# driverV3.net
KiCad netlist of a schematic drawn in EAGLE
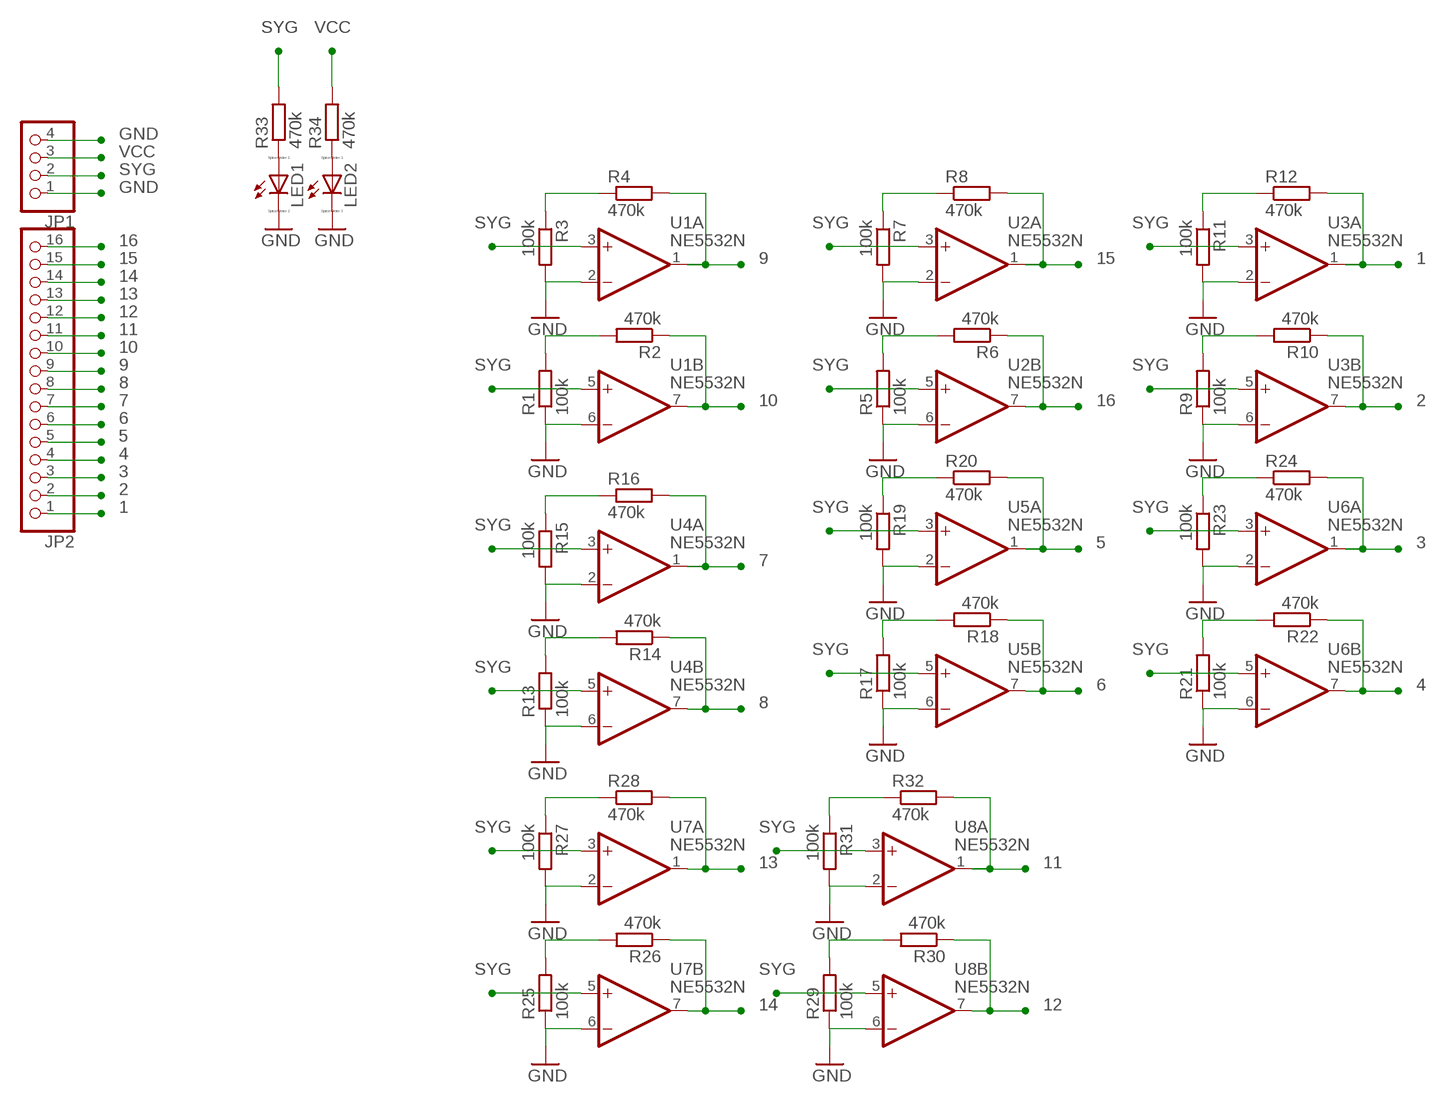
[diagram p0: schematic, sheet 1]

(export (version "E")
  (design (tool "Eeschema 10.0.6"))
  (components
    (comp (ref "JP1")
      (value "PINHD-1X4")
      (footprint "eagle-import:1X04")
      (libsource (lib "eagle-import") (part "PINHD-1X4"))
    )
    (comp (ref "JP2")
      (value "PINHD-1X16")
      (footprint "eagle-import:1X16")
      (libsource (lib "eagle-import") (part "PINHD-1X16"))
    )
    (comp (ref "LED1")
      (value "LED_ELD260")
      (footprint "eagle-import:LED_LD260")
      (libsource (lib "eagle-import") (part "LED_ELD260"))
    )
    (comp (ref "LED2")
      (value "LED_ELD260")
      (footprint "eagle-import:LED_LD260")
      (libsource (lib "eagle-import") (part "LED_ELD260"))
    )
    (comp (ref "R1")
      (value "100k")
      (footprint "eagle-import:0204_7")
      (libsource (lib "eagle-import") (part "R-EU_0204/7"))
    )
    (comp (ref "R2")
      (value "470k")
      (footprint "eagle-import:0204_7")
      (libsource (lib "eagle-import") (part "R-EU_0204/7"))
    )
    (comp (ref "R3")
      (value "100k")
      (footprint "eagle-import:0204_7")
      (libsource (lib "eagle-import") (part "R-EU_0204/7"))
    )
    (comp (ref "R4")
      (value "470k")
      (footprint "eagle-import:0204_7")
      (libsource (lib "eagle-import") (part "R-EU_0204/7"))
    )
    (comp (ref "R5")
      (value "100k")
      (footprint "eagle-import:0204_7")
      (libsource (lib "eagle-import") (part "R-EU_0204/7"))
    )
    (comp (ref "R6")
      (value "470k")
      (footprint "eagle-import:0204_7")
      (libsource (lib "eagle-import") (part "R-EU_0204/7"))
    )
    (comp (ref "R7")
      (value "100k")
      (footprint "eagle-import:0204_7")
      (libsource (lib "eagle-import") (part "R-EU_0204/7"))
    )
    (comp (ref "R8")
      (value "470k")
      (footprint "eagle-import:0204_7")
      (libsource (lib "eagle-import") (part "R-EU_0204/7"))
    )
    (comp (ref "R9")
      (value "100k")
      (footprint "eagle-import:0204_7")
      (libsource (lib "eagle-import") (part "R-EU_0204/7"))
    )
    (comp (ref "R10")
      (value "470k")
      (footprint "eagle-import:0204_7")
      (libsource (lib "eagle-import") (part "R-EU_0204/7"))
    )
    (comp (ref "R11")
      (value "100k")
      (footprint "eagle-import:0204_7")
      (libsource (lib "eagle-import") (part "R-EU_0204/7"))
    )
    (comp (ref "R12")
      (value "470k")
      (footprint "eagle-import:0204_7")
      (libsource (lib "eagle-import") (part "R-EU_0204/7"))
    )
    (comp (ref "R13")
      (value "100k")
      (footprint "eagle-import:0204_7")
      (libsource (lib "eagle-import") (part "R-EU_0204/7"))
    )
    (comp (ref "R14")
      (value "470k")
      (footprint "eagle-import:0204_7")
      (libsource (lib "eagle-import") (part "R-EU_0204/7"))
    )
    (comp (ref "R15")
      (value "100k")
      (footprint "eagle-import:0204_7")
      (libsource (lib "eagle-import") (part "R-EU_0204/7"))
    )
    (comp (ref "R16")
      (value "470k")
      (footprint "eagle-import:0204_7")
      (libsource (lib "eagle-import") (part "R-EU_0204/7"))
    )
    (comp (ref "R17")
      (value "100k")
      (footprint "eagle-import:0204_7")
      (libsource (lib "eagle-import") (part "R-EU_0204/7"))
    )
    (comp (ref "R18")
      (value "470k")
      (footprint "eagle-import:0204_7")
      (libsource (lib "eagle-import") (part "R-EU_0204/7"))
    )
    (comp (ref "R19")
      (value "100k")
      (footprint "eagle-import:0204_7")
      (libsource (lib "eagle-import") (part "R-EU_0204/7"))
    )
    (comp (ref "R20")
      (value "470k")
      (footprint "eagle-import:0204_7")
      (libsource (lib "eagle-import") (part "R-EU_0204/7"))
    )
    (comp (ref "R21")
      (value "100k")
      (footprint "eagle-import:0204_7")
      (libsource (lib "eagle-import") (part "R-EU_0204/7"))
    )
    (comp (ref "R22")
      (value "470k")
      (footprint "eagle-import:0204_7")
      (libsource (lib "eagle-import") (part "R-EU_0204/7"))
    )
    (comp (ref "R23")
      (value "100k")
      (footprint "eagle-import:0204_7")
      (libsource (lib "eagle-import") (part "R-EU_0204/7"))
    )
    (comp (ref "R24")
      (value "470k")
      (footprint "eagle-import:0204_7")
      (libsource (lib "eagle-import") (part "R-EU_0204/7"))
    )
    (comp (ref "R25")
      (value "100k")
      (footprint "eagle-import:0204_7")
      (libsource (lib "eagle-import") (part "R-EU_0204/7"))
    )
    (comp (ref "R26")
      (value "470k")
      (footprint "eagle-import:0204_7")
      (libsource (lib "eagle-import") (part "R-EU_0204/7"))
    )
    (comp (ref "R27")
      (value "100k")
      (footprint "eagle-import:0204_7")
      (libsource (lib "eagle-import") (part "R-EU_0204/7"))
    )
    (comp (ref "R28")
      (value "470k")
      (footprint "eagle-import:0204_7")
      (libsource (lib "eagle-import") (part "R-EU_0204/7"))
    )
    (comp (ref "R29")
      (value "100k")
      (footprint "eagle-import:0204_7")
      (libsource (lib "eagle-import") (part "R-EU_0204/7"))
    )
    (comp (ref "R30")
      (value "470k")
      (footprint "eagle-import:0204_7")
      (libsource (lib "eagle-import") (part "R-EU_0204/7"))
    )
    (comp (ref "R31")
      (value "100k")
      (footprint "eagle-import:0204_7")
      (libsource (lib "eagle-import") (part "R-EU_0204/7"))
    )
    (comp (ref "R32")
      (value "470k")
      (footprint "eagle-import:0204_7")
      (libsource (lib "eagle-import") (part "R-EU_0204/7"))
    )
    (comp (ref "R33")
      (value "470k")
      (footprint "eagle-import:0204_7")
      (libsource (lib "eagle-import") (part "R-EU_0204/7"))
    )
    (comp (ref "R34")
      (value "470k")
      (footprint "eagle-import:0204_7")
      (libsource (lib "eagle-import") (part "R-EU_0204/7"))
    )
    (comp (ref "U1")
      (value "NE5532N")
      (footprint "eagle-import:DIL08")
      (libsource (lib "eagle-import") (part "NE5532N"))
    )
    (comp (ref "U2")
      (value "NE5532N")
      (footprint "eagle-import:DIL08")
      (libsource (lib "eagle-import") (part "NE5532N"))
    )
    (comp (ref "U3")
      (value "NE5532N")
      (footprint "eagle-import:DIL08")
      (libsource (lib "eagle-import") (part "NE5532N"))
    )
    (comp (ref "U4")
      (value "NE5532N")
      (footprint "eagle-import:DIL08")
      (libsource (lib "eagle-import") (part "NE5532N"))
    )
    (comp (ref "U5")
      (value "NE5532N")
      (footprint "eagle-import:DIL08")
      (libsource (lib "eagle-import") (part "NE5532N"))
    )
    (comp (ref "U6")
      (value "NE5532N")
      (footprint "eagle-import:DIL08")
      (libsource (lib "eagle-import") (part "NE5532N"))
    )
    (comp (ref "U7")
      (value "NE5532N")
      (footprint "eagle-import:DIL08")
      (libsource (lib "eagle-import") (part "NE5532N"))
    )
    (comp (ref "U8")
      (value "NE5532N")
      (footprint "eagle-import:DIL08")
      (libsource (lib "eagle-import") (part "NE5532N"))
    )
  )
  (nets
    (net (code "1") (name "/1") (class "Default")
      (node (ref "JP2") (pin "1") (pinfunction "1_1") (pintype "passive"))
      (node (ref "R12") (pin "2") (pinfunction "2_2") (pintype "passive"))
      (node (ref "U3") (pin "1") (pinfunction "OUT_1") (pintype "output"))
    )
    (net (code "2") (name "/2") (class "Default")
      (node (ref "JP2") (pin "2") (pinfunction "2_2") (pintype "passive"))
      (node (ref "R10") (pin "1") (pinfunction "1_1") (pintype "passive"))
      (node (ref "U3") (pin "7") (pinfunction "OUT_7") (pintype "output"))
    )
    (net (code "3") (name "/3") (class "Default")
      (node (ref "JP2") (pin "3") (pinfunction "3_3") (pintype "passive"))
      (node (ref "R24") (pin "2") (pinfunction "2_2") (pintype "passive"))
      (node (ref "U6") (pin "1") (pinfunction "OUT_1") (pintype "output"))
    )
    (net (code "4") (name "/4") (class "Default")
      (node (ref "JP2") (pin "4") (pinfunction "4_4") (pintype "passive"))
      (node (ref "R22") (pin "1") (pinfunction "1_1") (pintype "passive"))
      (node (ref "U6") (pin "7") (pinfunction "OUT_7") (pintype "output"))
    )
    (net (code "5") (name "/5") (class "Default")
      (node (ref "JP2") (pin "5") (pinfunction "5_5") (pintype "passive"))
      (node (ref "R20") (pin "2") (pinfunction "2_2") (pintype "passive"))
      (node (ref "U5") (pin "1") (pinfunction "OUT_1") (pintype "output"))
    )
    (net (code "6") (name "/6") (class "Default")
      (node (ref "JP2") (pin "6") (pinfunction "6_6") (pintype "passive"))
      (node (ref "R18") (pin "1") (pinfunction "1_1") (pintype "passive"))
      (node (ref "U5") (pin "7") (pinfunction "OUT_7") (pintype "output"))
    )
    (net (code "7") (name "/7") (class "Default")
      (node (ref "JP2") (pin "7") (pinfunction "7_7") (pintype "passive"))
      (node (ref "R16") (pin "2") (pinfunction "2_2") (pintype "passive"))
      (node (ref "U4") (pin "1") (pinfunction "OUT_1") (pintype "output"))
    )
    (net (code "8") (name "/8") (class "Default")
      (node (ref "JP2") (pin "8") (pinfunction "8_8") (pintype "passive"))
      (node (ref "R14") (pin "1") (pinfunction "1_1") (pintype "passive"))
      (node (ref "U4") (pin "7") (pinfunction "OUT_7") (pintype "output"))
    )
    (net (code "9") (name "/9") (class "Default")
      (node (ref "JP2") (pin "9") (pinfunction "9_9") (pintype "passive"))
      (node (ref "R4") (pin "2") (pinfunction "2_2") (pintype "passive"))
      (node (ref "U1") (pin "1") (pinfunction "OUT_1") (pintype "output"))
    )
    (net (code "10") (name "/10") (class "Default")
      (node (ref "JP2") (pin "10") (pinfunction "10_10") (pintype "passive"))
      (node (ref "R2") (pin "1") (pinfunction "1_1") (pintype "passive"))
      (node (ref "U1") (pin "7") (pinfunction "OUT_7") (pintype "output"))
    )
    (net (code "11") (name "/11") (class "Default")
      (node (ref "JP2") (pin "11") (pinfunction "11_11") (pintype "passive"))
      (node (ref "R32") (pin "2") (pinfunction "2_2") (pintype "passive"))
      (node (ref "U8") (pin "1") (pinfunction "OUT_1") (pintype "output"))
    )
    (net (code "12") (name "/12") (class "Default")
      (node (ref "JP2") (pin "12") (pinfunction "12_12") (pintype "passive"))
      (node (ref "R30") (pin "1") (pinfunction "1_1") (pintype "passive"))
      (node (ref "U8") (pin "7") (pinfunction "OUT_7") (pintype "output"))
    )
    (net (code "13") (name "/13") (class "Default")
      (node (ref "JP2") (pin "13") (pinfunction "13_13") (pintype "passive"))
      (node (ref "R28") (pin "2") (pinfunction "2_2") (pintype "passive"))
      (node (ref "U7") (pin "1") (pinfunction "OUT_1") (pintype "output"))
    )
    (net (code "14") (name "/14") (class "Default")
      (node (ref "JP2") (pin "14") (pinfunction "14_14") (pintype "passive"))
      (node (ref "R26") (pin "1") (pinfunction "1_1") (pintype "passive"))
      (node (ref "U7") (pin "7") (pinfunction "OUT_7") (pintype "output"))
    )
    (net (code "15") (name "/15") (class "Default")
      (node (ref "JP2") (pin "15") (pinfunction "15_15") (pintype "passive"))
      (node (ref "R8") (pin "2") (pinfunction "2_2") (pintype "passive"))
      (node (ref "U2") (pin "1") (pinfunction "OUT_1") (pintype "output"))
    )
    (net (code "16") (name "/16") (class "Default")
      (node (ref "JP2") (pin "16") (pinfunction "16_16") (pintype "passive"))
      (node (ref "R6") (pin "1") (pinfunction "1_1") (pintype "passive"))
      (node (ref "U2") (pin "7") (pinfunction "OUT_7") (pintype "output"))
    )
    (net (code "17") (name "/SYG") (class "Default")
      (node (ref "JP1") (pin "2") (pinfunction "2_2") (pintype "passive"))
      (node (ref "R33") (pin "2") (pinfunction "2_2") (pintype "passive"))
      (node (ref "U1") (pin "3") (pinfunction "+IN_3") (pintype "input"))
      (node (ref "U1") (pin "5") (pinfunction "+IN_5") (pintype "input"))
      (node (ref "U2") (pin "3") (pinfunction "+IN_3") (pintype "input"))
      (node (ref "U2") (pin "5") (pinfunction "+IN_5") (pintype "input"))
      (node (ref "U3") (pin "3") (pinfunction "+IN_3") (pintype "input"))
      (node (ref "U3") (pin "5") (pinfunction "+IN_5") (pintype "input"))
      (node (ref "U4") (pin "3") (pinfunction "+IN_3") (pintype "input"))
      (node (ref "U4") (pin "5") (pinfunction "+IN_5") (pintype "input"))
      (node (ref "U5") (pin "3") (pinfunction "+IN_3") (pintype "input"))
      (node (ref "U5") (pin "5") (pinfunction "+IN_5") (pintype "input"))
      (node (ref "U6") (pin "3") (pinfunction "+IN_3") (pintype "input"))
      (node (ref "U6") (pin "5") (pinfunction "+IN_5") (pintype "input"))
      (node (ref "U7") (pin "3") (pinfunction "+IN_3") (pintype "input"))
      (node (ref "U7") (pin "5") (pinfunction "+IN_5") (pintype "input"))
      (node (ref "U8") (pin "3") (pinfunction "+IN_3") (pintype "input"))
      (node (ref "U8") (pin "5") (pinfunction "+IN_5") (pintype "input"))
    )
    (net (code "18") (name "/VCC") (class "Default")
      (node (ref "JP1") (pin "3") (pinfunction "3_3") (pintype "passive"))
      (node (ref "R34") (pin "2") (pinfunction "2_2") (pintype "passive"))
    )
    (net (code "19") (name "GND") (class "Default")
      (node (ref "JP1") (pin "1") (pinfunction "1_1") (pintype "passive"))
      (node (ref "JP1") (pin "4") (pinfunction "4_4") (pintype "passive"))
      (node (ref "LED1") (pin "K") (pinfunction "C_K") (pintype "passive"))
      (node (ref "LED2") (pin "K") (pinfunction "C_K") (pintype "passive"))
      (node (ref "R1") (pin "1") (pinfunction "1_1") (pintype "passive"))
      (node (ref "R11") (pin "2") (pinfunction "2_2") (pintype "passive"))
      (node (ref "R13") (pin "1") (pinfunction "1_1") (pintype "passive"))
      (node (ref "R15") (pin "2") (pinfunction "2_2") (pintype "passive"))
      (node (ref "R17") (pin "1") (pinfunction "1_1") (pintype "passive"))
      (node (ref "R19") (pin "2") (pinfunction "2_2") (pintype "passive"))
      (node (ref "R21") (pin "1") (pinfunction "1_1") (pintype "passive"))
      (node (ref "R23") (pin "2") (pinfunction "2_2") (pintype "passive"))
      (node (ref "R25") (pin "1") (pinfunction "1_1") (pintype "passive"))
      (node (ref "R27") (pin "2") (pinfunction "2_2") (pintype "passive"))
      (node (ref "R29") (pin "1") (pinfunction "1_1") (pintype "passive"))
      (node (ref "R3") (pin "2") (pinfunction "2_2") (pintype "passive"))
      (node (ref "R31") (pin "2") (pinfunction "2_2") (pintype "passive"))
      (node (ref "R5") (pin "1") (pinfunction "1_1") (pintype "passive"))
      (node (ref "R7") (pin "2") (pinfunction "2_2") (pintype "passive"))
      (node (ref "R9") (pin "1") (pinfunction "1_1") (pintype "passive"))
      (node (ref "U1") (pin "2") (pinfunction "-IN_2") (pintype "input"))
      (node (ref "U1") (pin "6") (pinfunction "-IN_6") (pintype "input"))
      (node (ref "U2") (pin "2") (pinfunction "-IN_2") (pintype "input"))
      (node (ref "U2") (pin "6") (pinfunction "-IN_6") (pintype "input"))
      (node (ref "U3") (pin "2") (pinfunction "-IN_2") (pintype "input"))
      (node (ref "U3") (pin "6") (pinfunction "-IN_6") (pintype "input"))
      (node (ref "U4") (pin "2") (pinfunction "-IN_2") (pintype "input"))
      (node (ref "U4") (pin "6") (pinfunction "-IN_6") (pintype "input"))
      (node (ref "U5") (pin "2") (pinfunction "-IN_2") (pintype "input"))
      (node (ref "U5") (pin "6") (pinfunction "-IN_6") (pintype "input"))
      (node (ref "U6") (pin "2") (pinfunction "-IN_2") (pintype "input"))
      (node (ref "U6") (pin "6") (pinfunction "-IN_6") (pintype "input"))
      (node (ref "U7") (pin "2") (pinfunction "-IN_2") (pintype "input"))
      (node (ref "U7") (pin "6") (pinfunction "-IN_6") (pintype "input"))
      (node (ref "U8") (pin "2") (pinfunction "-IN_2") (pintype "input"))
      (node (ref "U8") (pin "6") (pinfunction "-IN_6") (pintype "input"))
    )
    (net (code "20") (name "Net-(LED1-PadA)") (class "Default")
      (node (ref "LED1") (pin "A") (pinfunction "A_A") (pintype "passive"))
      (node (ref "R33") (pin "1") (pinfunction "1_1") (pintype "passive"))
    )
    (net (code "21") (name "Net-(LED2-PadA)") (class "Default")
      (node (ref "LED2") (pin "A") (pinfunction "A_A") (pintype "passive"))
      (node (ref "R34") (pin "1") (pinfunction "1_1") (pintype "passive"))
    )
    (net (code "22") (name "Net-(R1-Pad2)") (class "Default")
      (node (ref "R1") (pin "2") (pinfunction "2_2") (pintype "passive"))
      (node (ref "R2") (pin "2") (pinfunction "2_2") (pintype "passive"))
    )
    (net (code "23") (name "Net-(R3-Pad1)") (class "Default")
      (node (ref "R3") (pin "1") (pinfunction "1_1") (pintype "passive"))
      (node (ref "R4") (pin "1") (pinfunction "1_1") (pintype "passive"))
    )
    (net (code "24") (name "Net-(R5-Pad2)") (class "Default")
      (node (ref "R5") (pin "2") (pinfunction "2_2") (pintype "passive"))
      (node (ref "R6") (pin "2") (pinfunction "2_2") (pintype "passive"))
    )
    (net (code "25") (name "Net-(R7-Pad1)") (class "Default")
      (node (ref "R7") (pin "1") (pinfunction "1_1") (pintype "passive"))
      (node (ref "R8") (pin "1") (pinfunction "1_1") (pintype "passive"))
    )
    (net (code "26") (name "Net-(R10-Pad2)") (class "Default")
      (node (ref "R10") (pin "2") (pinfunction "2_2") (pintype "passive"))
      (node (ref "R9") (pin "2") (pinfunction "2_2") (pintype "passive"))
    )
    (net (code "27") (name "Net-(R11-Pad1)") (class "Default")
      (node (ref "R11") (pin "1") (pinfunction "1_1") (pintype "passive"))
      (node (ref "R12") (pin "1") (pinfunction "1_1") (pintype "passive"))
    )
    (net (code "28") (name "Net-(R13-Pad2)") (class "Default")
      (node (ref "R13") (pin "2") (pinfunction "2_2") (pintype "passive"))
      (node (ref "R14") (pin "2") (pinfunction "2_2") (pintype "passive"))
    )
    (net (code "29") (name "Net-(R15-Pad1)") (class "Default")
      (node (ref "R15") (pin "1") (pinfunction "1_1") (pintype "passive"))
      (node (ref "R16") (pin "1") (pinfunction "1_1") (pintype "passive"))
    )
    (net (code "30") (name "Net-(R17-Pad2)") (class "Default")
      (node (ref "R17") (pin "2") (pinfunction "2_2") (pintype "passive"))
      (node (ref "R18") (pin "2") (pinfunction "2_2") (pintype "passive"))
    )
    (net (code "31") (name "Net-(R19-Pad1)") (class "Default")
      (node (ref "R19") (pin "1") (pinfunction "1_1") (pintype "passive"))
      (node (ref "R20") (pin "1") (pinfunction "1_1") (pintype "passive"))
    )
    (net (code "32") (name "Net-(R21-Pad2)") (class "Default")
      (node (ref "R21") (pin "2") (pinfunction "2_2") (pintype "passive"))
      (node (ref "R22") (pin "2") (pinfunction "2_2") (pintype "passive"))
    )
    (net (code "33") (name "Net-(R23-Pad1)") (class "Default")
      (node (ref "R23") (pin "1") (pinfunction "1_1") (pintype "passive"))
      (node (ref "R24") (pin "1") (pinfunction "1_1") (pintype "passive"))
    )
    (net (code "34") (name "Net-(R25-Pad2)") (class "Default")
      (node (ref "R25") (pin "2") (pinfunction "2_2") (pintype "passive"))
      (node (ref "R26") (pin "2") (pinfunction "2_2") (pintype "passive"))
    )
    (net (code "35") (name "Net-(R27-Pad1)") (class "Default")
      (node (ref "R27") (pin "1") (pinfunction "1_1") (pintype "passive"))
      (node (ref "R28") (pin "1") (pinfunction "1_1") (pintype "passive"))
    )
    (net (code "36") (name "Net-(R29-Pad2)") (class "Default")
      (node (ref "R29") (pin "2") (pinfunction "2_2") (pintype "passive"))
      (node (ref "R30") (pin "2") (pinfunction "2_2") (pintype "passive"))
    )
    (net (code "37") (name "Net-(R31-Pad1)") (class "Default")
      (node (ref "R31") (pin "1") (pinfunction "1_1") (pintype "passive"))
      (node (ref "R32") (pin "1") (pinfunction "1_1") (pintype "passive"))
    )
  )
)
